# PGA44DIP44.net
KiCad netlist of a schematic drawn in EAGLE
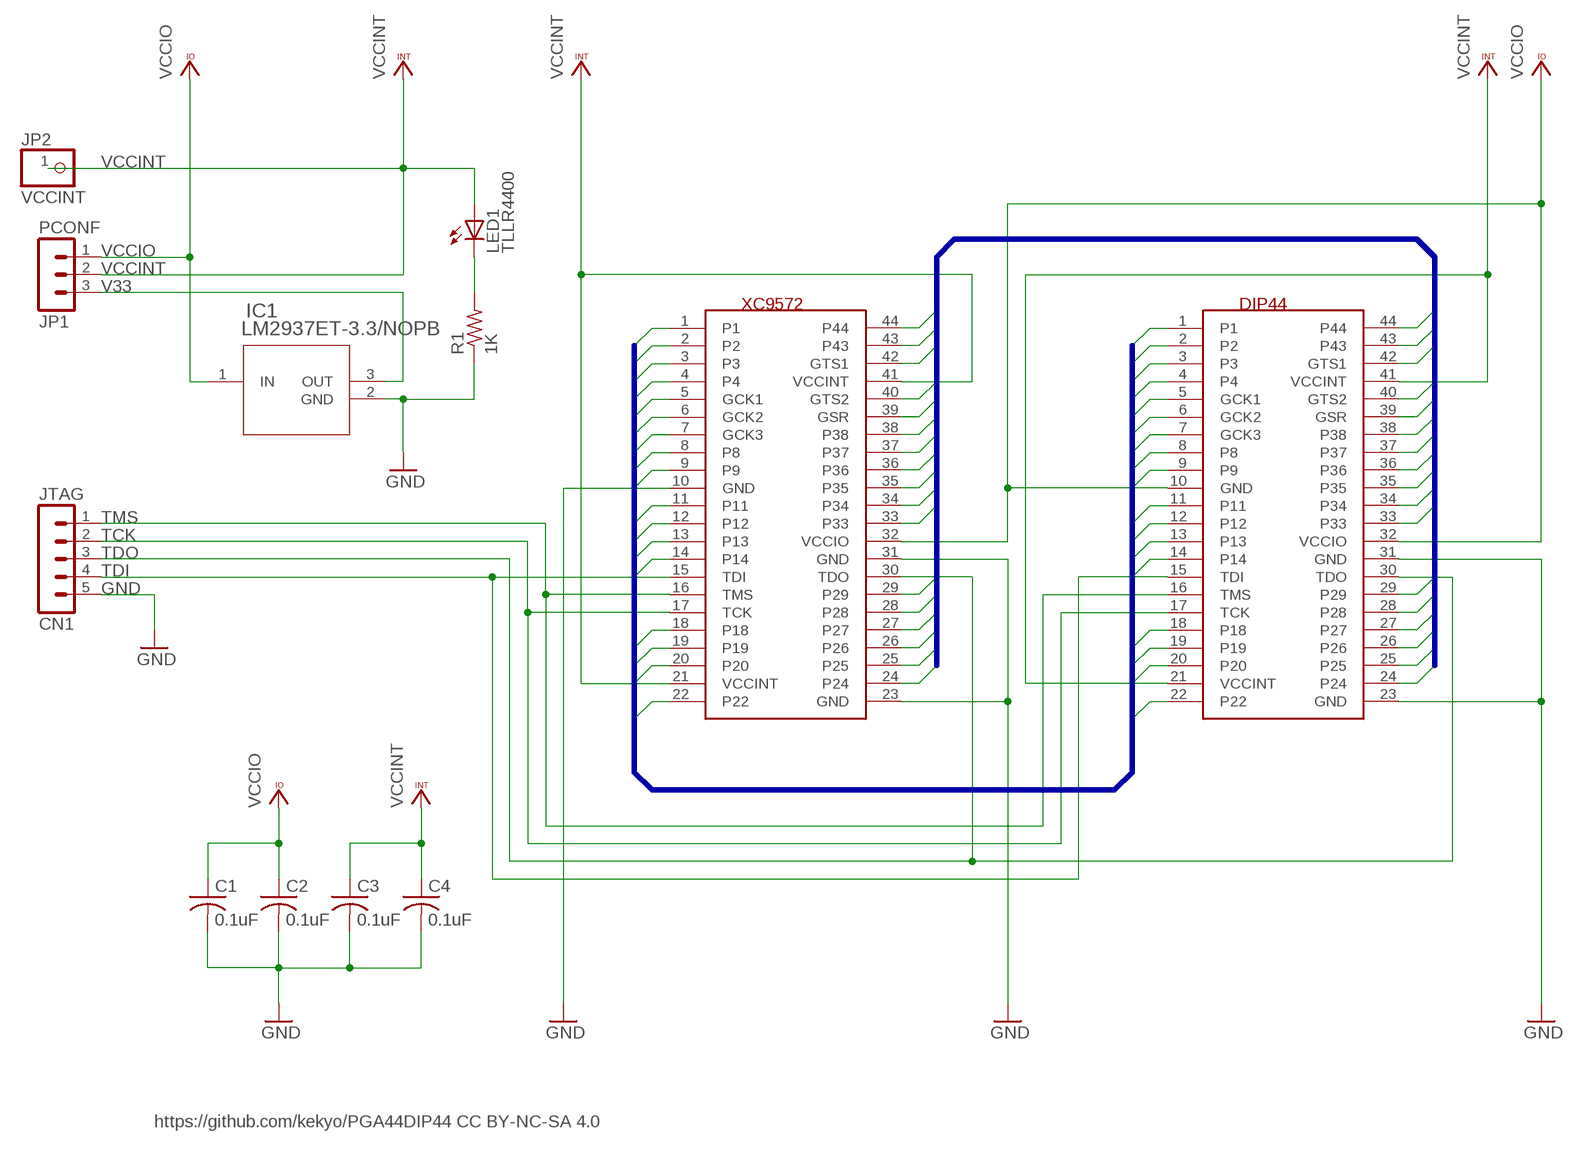
[diagram p0: schematic, sheet 1]

(export (version "E")
  (design (tool "Eeschema 10.0.6"))
  (components
    (comp (ref "C1")
      (value "0.1uF")
      (footprint "eagle-import:C050-024X044")
      (libsource (lib "eagle-import") (part "C-US050-024X044"))
    )
    (comp (ref "C2")
      (value "0.1uF")
      (footprint "eagle-import:C050-024X044")
      (libsource (lib "eagle-import") (part "C-US050-024X044"))
    )
    (comp (ref "C3")
      (value "0.1uF")
      (footprint "eagle-import:C050-024X044")
      (libsource (lib "eagle-import") (part "C-US050-024X044"))
    )
    (comp (ref "C4")
      (value "0.1uF")
      (footprint "eagle-import:C050-024X044")
      (libsource (lib "eagle-import") (part "C-US050-024X044"))
    )
    (comp (ref "CN1")
      (value "JTAG")
      (footprint "eagle-import:MA05-1")
      (libsource (lib "eagle-import") (part "MA05-1"))
    )
    (comp (ref "DIP44")
      (value "DIP44")
      (footprint "eagle-import:DIP44")
      (libsource (lib "eagle-import") (part "DIP44"))
    )
    (comp (ref "IC1")
      (value "LM2937ET-3.3/NOPB")
      (footprint "eagle-import:T03B")
      (fields (field (name "MANUFACTURER_PART_NUMBER") "lm2937et3_3nopb"))
      (libsource (lib "eagle-import") (part "LM2937ET-3.3/NOPB"))
    )
    (comp (ref "JP1")
      (value "PCONF")
      (footprint "eagle-import:MA03-1")
      (libsource (lib "eagle-import") (part "MA03-1"))
    )
    (comp (ref "JP2")
      (value "VCCINT")
      (footprint "eagle-import:1X01")
      (libsource (lib "eagle-import") (part "PINHD-1X1"))
    )
    (comp (ref "LED1")
      (value "TLLR4400")
      (footprint "eagle-import:LED3MM")
      (fields (field (name "MF") "VISHAY SEMICONDUCTOR"))
      (libsource (lib "eagle-import") (part "TLLR4400"))
    )
    (comp (ref "R1")
      (value "1K")
      (footprint "eagle-import:0207_2V")
      (libsource (lib "eagle-import") (part "R-US_0207/2V"))
    )
    (comp (ref "XC9572")
      (value "PGA44")
      (footprint "eagle-import:PGA44")
      (libsource (lib "eagle-import") (part "PGA44"))
    )
  )
  (nets
    (net (code "1") (name "/L1") (class "Default")
      (node (ref "DIP44") (pin "1") (pinfunction "P1_1") (pintype "bidirectional"))
      (node (ref "XC9572") (pin "1") (pinfunction "P1_1") (pintype "bidirectional"))
    )
    (net (code "2") (name "/L2") (class "Default")
      (node (ref "DIP44") (pin "2") (pinfunction "P2_2") (pintype "bidirectional"))
      (node (ref "XC9572") (pin "2") (pinfunction "P2_2") (pintype "bidirectional"))
    )
    (net (code "3") (name "/L3") (class "Default")
      (node (ref "DIP44") (pin "3") (pinfunction "P3_3") (pintype "bidirectional"))
      (node (ref "XC9572") (pin "3") (pinfunction "P3_3") (pintype "bidirectional"))
    )
    (net (code "4") (name "/L4") (class "Default")
      (node (ref "DIP44") (pin "4") (pinfunction "P4_4") (pintype "bidirectional"))
      (node (ref "XC9572") (pin "4") (pinfunction "P4_4") (pintype "bidirectional"))
    )
    (net (code "5") (name "/L5") (class "Default")
      (node (ref "DIP44") (pin "5") (pinfunction "GCK1_5") (pintype "bidirectional"))
      (node (ref "XC9572") (pin "5") (pinfunction "GCK1_5") (pintype "bidirectional"))
    )
    (net (code "6") (name "/L6") (class "Default")
      (node (ref "DIP44") (pin "6") (pinfunction "GCK2_6") (pintype "bidirectional"))
      (node (ref "XC9572") (pin "6") (pinfunction "GCK2_6") (pintype "bidirectional"))
    )
    (net (code "7") (name "/L7") (class "Default")
      (node (ref "DIP44") (pin "7") (pinfunction "GCK3_7") (pintype "bidirectional"))
      (node (ref "XC9572") (pin "7") (pinfunction "GCK3_7") (pintype "bidirectional"))
    )
    (net (code "8") (name "/L8") (class "Default")
      (node (ref "DIP44") (pin "8") (pinfunction "P8_8") (pintype "bidirectional"))
      (node (ref "XC9572") (pin "8") (pinfunction "P8_8") (pintype "bidirectional"))
    )
    (net (code "9") (name "/L9") (class "Default")
      (node (ref "DIP44") (pin "9") (pinfunction "P9_9") (pintype "bidirectional"))
      (node (ref "XC9572") (pin "9") (pinfunction "P9_9") (pintype "bidirectional"))
    )
    (net (code "10") (name "/L11") (class "Default")
      (node (ref "DIP44") (pin "11") (pinfunction "P11_11") (pintype "bidirectional"))
      (node (ref "XC9572") (pin "11") (pinfunction "P11_11") (pintype "bidirectional"))
    )
    (net (code "11") (name "/L12") (class "Default")
      (node (ref "DIP44") (pin "12") (pinfunction "P12_12") (pintype "bidirectional"))
      (node (ref "XC9572") (pin "12") (pinfunction "P12_12") (pintype "bidirectional"))
    )
    (net (code "12") (name "/L13") (class "Default")
      (node (ref "DIP44") (pin "13") (pinfunction "P13_13") (pintype "bidirectional"))
      (node (ref "XC9572") (pin "13") (pinfunction "P13_13") (pintype "bidirectional"))
    )
    (net (code "13") (name "/L14") (class "Default")
      (node (ref "DIP44") (pin "14") (pinfunction "P14_14") (pintype "bidirectional"))
      (node (ref "XC9572") (pin "14") (pinfunction "P14_14") (pintype "bidirectional"))
    )
    (net (code "14") (name "/L18") (class "Default")
      (node (ref "DIP44") (pin "18") (pinfunction "P18_18") (pintype "bidirectional"))
      (node (ref "XC9572") (pin "18") (pinfunction "P18_18") (pintype "bidirectional"))
    )
    (net (code "15") (name "/L19") (class "Default")
      (node (ref "DIP44") (pin "19") (pinfunction "P19_19") (pintype "bidirectional"))
      (node (ref "XC9572") (pin "19") (pinfunction "P19_19") (pintype "bidirectional"))
    )
    (net (code "16") (name "/L20") (class "Default")
      (node (ref "DIP44") (pin "20") (pinfunction "P20_20") (pintype "bidirectional"))
      (node (ref "XC9572") (pin "20") (pinfunction "P20_20") (pintype "bidirectional"))
    )
    (net (code "17") (name "/L22") (class "Default")
      (node (ref "DIP44") (pin "22") (pinfunction "P22_22") (pintype "bidirectional"))
      (node (ref "XC9572") (pin "22") (pinfunction "P22_22") (pintype "bidirectional"))
    )
    (net (code "18") (name "/L24") (class "Default")
      (node (ref "DIP44") (pin "24") (pinfunction "P24_24") (pintype "bidirectional"))
      (node (ref "XC9572") (pin "24") (pinfunction "P24_24") (pintype "bidirectional"))
    )
    (net (code "19") (name "/L25") (class "Default")
      (node (ref "DIP44") (pin "25") (pinfunction "P25_25") (pintype "bidirectional"))
      (node (ref "XC9572") (pin "25") (pinfunction "P25_25") (pintype "bidirectional"))
    )
    (net (code "20") (name "/L26") (class "Default")
      (node (ref "DIP44") (pin "26") (pinfunction "P26_26") (pintype "bidirectional"))
      (node (ref "XC9572") (pin "26") (pinfunction "P26_26") (pintype "bidirectional"))
    )
    (net (code "21") (name "/L27") (class "Default")
      (node (ref "DIP44") (pin "27") (pinfunction "P27_27") (pintype "bidirectional"))
      (node (ref "XC9572") (pin "27") (pinfunction "P27_27") (pintype "bidirectional"))
    )
    (net (code "22") (name "/L28") (class "Default")
      (node (ref "DIP44") (pin "28") (pinfunction "P28_28") (pintype "bidirectional"))
      (node (ref "XC9572") (pin "28") (pinfunction "P28_28") (pintype "bidirectional"))
    )
    (net (code "23") (name "/L29") (class "Default")
      (node (ref "DIP44") (pin "29") (pinfunction "P29_29") (pintype "bidirectional"))
      (node (ref "XC9572") (pin "29") (pinfunction "P29_29") (pintype "bidirectional"))
    )
    (net (code "24") (name "/L33") (class "Default")
      (node (ref "DIP44") (pin "33") (pinfunction "P33_33") (pintype "bidirectional"))
      (node (ref "XC9572") (pin "33") (pinfunction "P33_33") (pintype "bidirectional"))
    )
    (net (code "25") (name "/L34") (class "Default")
      (node (ref "DIP44") (pin "34") (pinfunction "P34_34") (pintype "bidirectional"))
      (node (ref "XC9572") (pin "34") (pinfunction "P34_34") (pintype "bidirectional"))
    )
    (net (code "26") (name "/L35") (class "Default")
      (node (ref "DIP44") (pin "35") (pinfunction "P35_35") (pintype "bidirectional"))
      (node (ref "XC9572") (pin "35") (pinfunction "P35_35") (pintype "bidirectional"))
    )
    (net (code "27") (name "/L36") (class "Default")
      (node (ref "DIP44") (pin "36") (pinfunction "P36_36") (pintype "bidirectional"))
      (node (ref "XC9572") (pin "36") (pinfunction "P36_36") (pintype "bidirectional"))
    )
    (net (code "28") (name "/L37") (class "Default")
      (node (ref "DIP44") (pin "37") (pinfunction "P37_37") (pintype "bidirectional"))
      (node (ref "XC9572") (pin "37") (pinfunction "P37_37") (pintype "bidirectional"))
    )
    (net (code "29") (name "/L38") (class "Default")
      (node (ref "DIP44") (pin "38") (pinfunction "P38_38") (pintype "bidirectional"))
      (node (ref "XC9572") (pin "38") (pinfunction "P38_38") (pintype "bidirectional"))
    )
    (net (code "30") (name "/L39") (class "Default")
      (node (ref "DIP44") (pin "39") (pinfunction "GSR_39") (pintype "bidirectional"))
      (node (ref "XC9572") (pin "39") (pinfunction "GSR_39") (pintype "bidirectional"))
    )
    (net (code "31") (name "/L40") (class "Default")
      (node (ref "DIP44") (pin "40") (pinfunction "GTS2_40") (pintype "bidirectional"))
      (node (ref "XC9572") (pin "40") (pinfunction "GTS2_40") (pintype "bidirectional"))
    )
    (net (code "32") (name "/L42") (class "Default")
      (node (ref "DIP44") (pin "42") (pinfunction "GTS1_42") (pintype "bidirectional"))
      (node (ref "XC9572") (pin "42") (pinfunction "GTS1_42") (pintype "bidirectional"))
    )
    (net (code "33") (name "/L43") (class "Default")
      (node (ref "DIP44") (pin "43") (pinfunction "P43_43") (pintype "bidirectional"))
      (node (ref "XC9572") (pin "43") (pinfunction "P43_43") (pintype "bidirectional"))
    )
    (net (code "34") (name "/L44") (class "Default")
      (node (ref "DIP44") (pin "44") (pinfunction "P44_44") (pintype "bidirectional"))
      (node (ref "XC9572") (pin "44") (pinfunction "P44_44") (pintype "bidirectional"))
    )
    (net (code "35") (name "/TCK") (class "Default")
      (node (ref "CN1") (pin "2") (pinfunction "2_2") (pintype "passive"))
      (node (ref "DIP44") (pin "17") (pinfunction "TCK_17") (pintype "bidirectional"))
      (node (ref "XC9572") (pin "17") (pinfunction "TCK_17") (pintype "bidirectional"))
    )
    (net (code "36") (name "/TDI") (class "Default")
      (node (ref "CN1") (pin "4") (pinfunction "4_4") (pintype "passive"))
      (node (ref "DIP44") (pin "15") (pinfunction "TDI_15") (pintype "bidirectional"))
      (node (ref "XC9572") (pin "15") (pinfunction "TDI_15") (pintype "bidirectional"))
    )
    (net (code "37") (name "/TDO") (class "Default")
      (node (ref "CN1") (pin "3") (pinfunction "3_3") (pintype "passive"))
      (node (ref "DIP44") (pin "30") (pinfunction "TDO_30") (pintype "bidirectional"))
      (node (ref "XC9572") (pin "30") (pinfunction "TDO_30") (pintype "bidirectional"))
    )
    (net (code "38") (name "/TMS") (class "Default")
      (node (ref "CN1") (pin "1") (pinfunction "1_1") (pintype "passive"))
      (node (ref "DIP44") (pin "16") (pinfunction "TMS_16") (pintype "bidirectional"))
      (node (ref "XC9572") (pin "16") (pinfunction "TMS_16") (pintype "bidirectional"))
    )
    (net (code "39") (name "/V33") (class "Default")
      (node (ref "IC1") (pin "3") (pinfunction "OUT_3") (pintype "power_in"))
      (node (ref "JP1") (pin "3") (pinfunction "3_3") (pintype "passive"))
    )
    (net (code "40") (name "GND") (class "Default")
      (node (ref "C1") (pin "2") (pinfunction "2_2") (pintype "passive"))
      (node (ref "C2") (pin "2") (pinfunction "2_2") (pintype "passive"))
      (node (ref "C3") (pin "2") (pinfunction "2_2") (pintype "passive"))
      (node (ref "C4") (pin "2") (pinfunction "2_2") (pintype "passive"))
      (node (ref "CN1") (pin "5") (pinfunction "5_5") (pintype "passive"))
      (node (ref "DIP44") (pin "23") (pinfunction "GND_23") (pintype "bidirectional"))
      (node (ref "DIP44") (pin "31") (pinfunction "GND_31") (pintype "bidirectional"))
      (node (ref "IC1") (pin "2") (pinfunction "GND_2") (pintype "power_in"))
      (node (ref "R1") (pin "1") (pinfunction "1_1") (pintype "passive"))
      (node (ref "XC9572") (pin "10") (pinfunction "GND_10") (pintype "bidirectional"))
      (node (ref "XC9572") (pin "23") (pinfunction "GND_23") (pintype "bidirectional"))
      (node (ref "XC9572") (pin "31") (pinfunction "GND_31") (pintype "bidirectional"))
    )
    (net (code "41") (name "Net-(LED1-C)") (class "Default")
      (node (ref "LED1") (pin "K") (pinfunction "C_K") (pintype "passive"))
      (node (ref "R1") (pin "2") (pinfunction "2_2") (pintype "passive"))
    )
    (net (code "42") (name "VCCINT") (class "Default")
      (node (ref "C3") (pin "1") (pinfunction "1_1") (pintype "passive"))
      (node (ref "C4") (pin "1") (pinfunction "1_1") (pintype "passive"))
      (node (ref "DIP44") (pin "21") (pinfunction "VCCINT_21") (pintype "bidirectional"))
      (node (ref "DIP44") (pin "41") (pinfunction "VCCINT_41") (pintype "bidirectional"))
      (node (ref "JP1") (pin "2") (pinfunction "2_2") (pintype "passive"))
      (node (ref "JP2") (pin "1") (pinfunction "1_1") (pintype "passive"))
      (node (ref "LED1") (pin "A") (pinfunction "A_A") (pintype "passive"))
      (node (ref "XC9572") (pin "21") (pinfunction "VCCINT_21") (pintype "bidirectional"))
      (node (ref "XC9572") (pin "41") (pinfunction "VCCINT_41") (pintype "bidirectional"))
    )
    (net (code "43") (name "VCCIO") (class "Default")
      (node (ref "C1") (pin "1") (pinfunction "1_1") (pintype "passive"))
      (node (ref "C2") (pin "1") (pinfunction "1_1") (pintype "passive"))
      (node (ref "DIP44") (pin "10") (pinfunction "GND_10") (pintype "bidirectional"))
      (node (ref "DIP44") (pin "32") (pinfunction "VCCIO_32") (pintype "bidirectional"))
      (node (ref "IC1") (pin "1") (pinfunction "IN_1") (pintype "power_in"))
      (node (ref "JP1") (pin "1") (pinfunction "1_1") (pintype "passive"))
      (node (ref "XC9572") (pin "32") (pinfunction "VCCIO_32") (pintype "bidirectional"))
    )
  )
)
